# ant2-usb-c-lipo-charger.net
KiCad netlist of a schematic drawn in Altium Designer
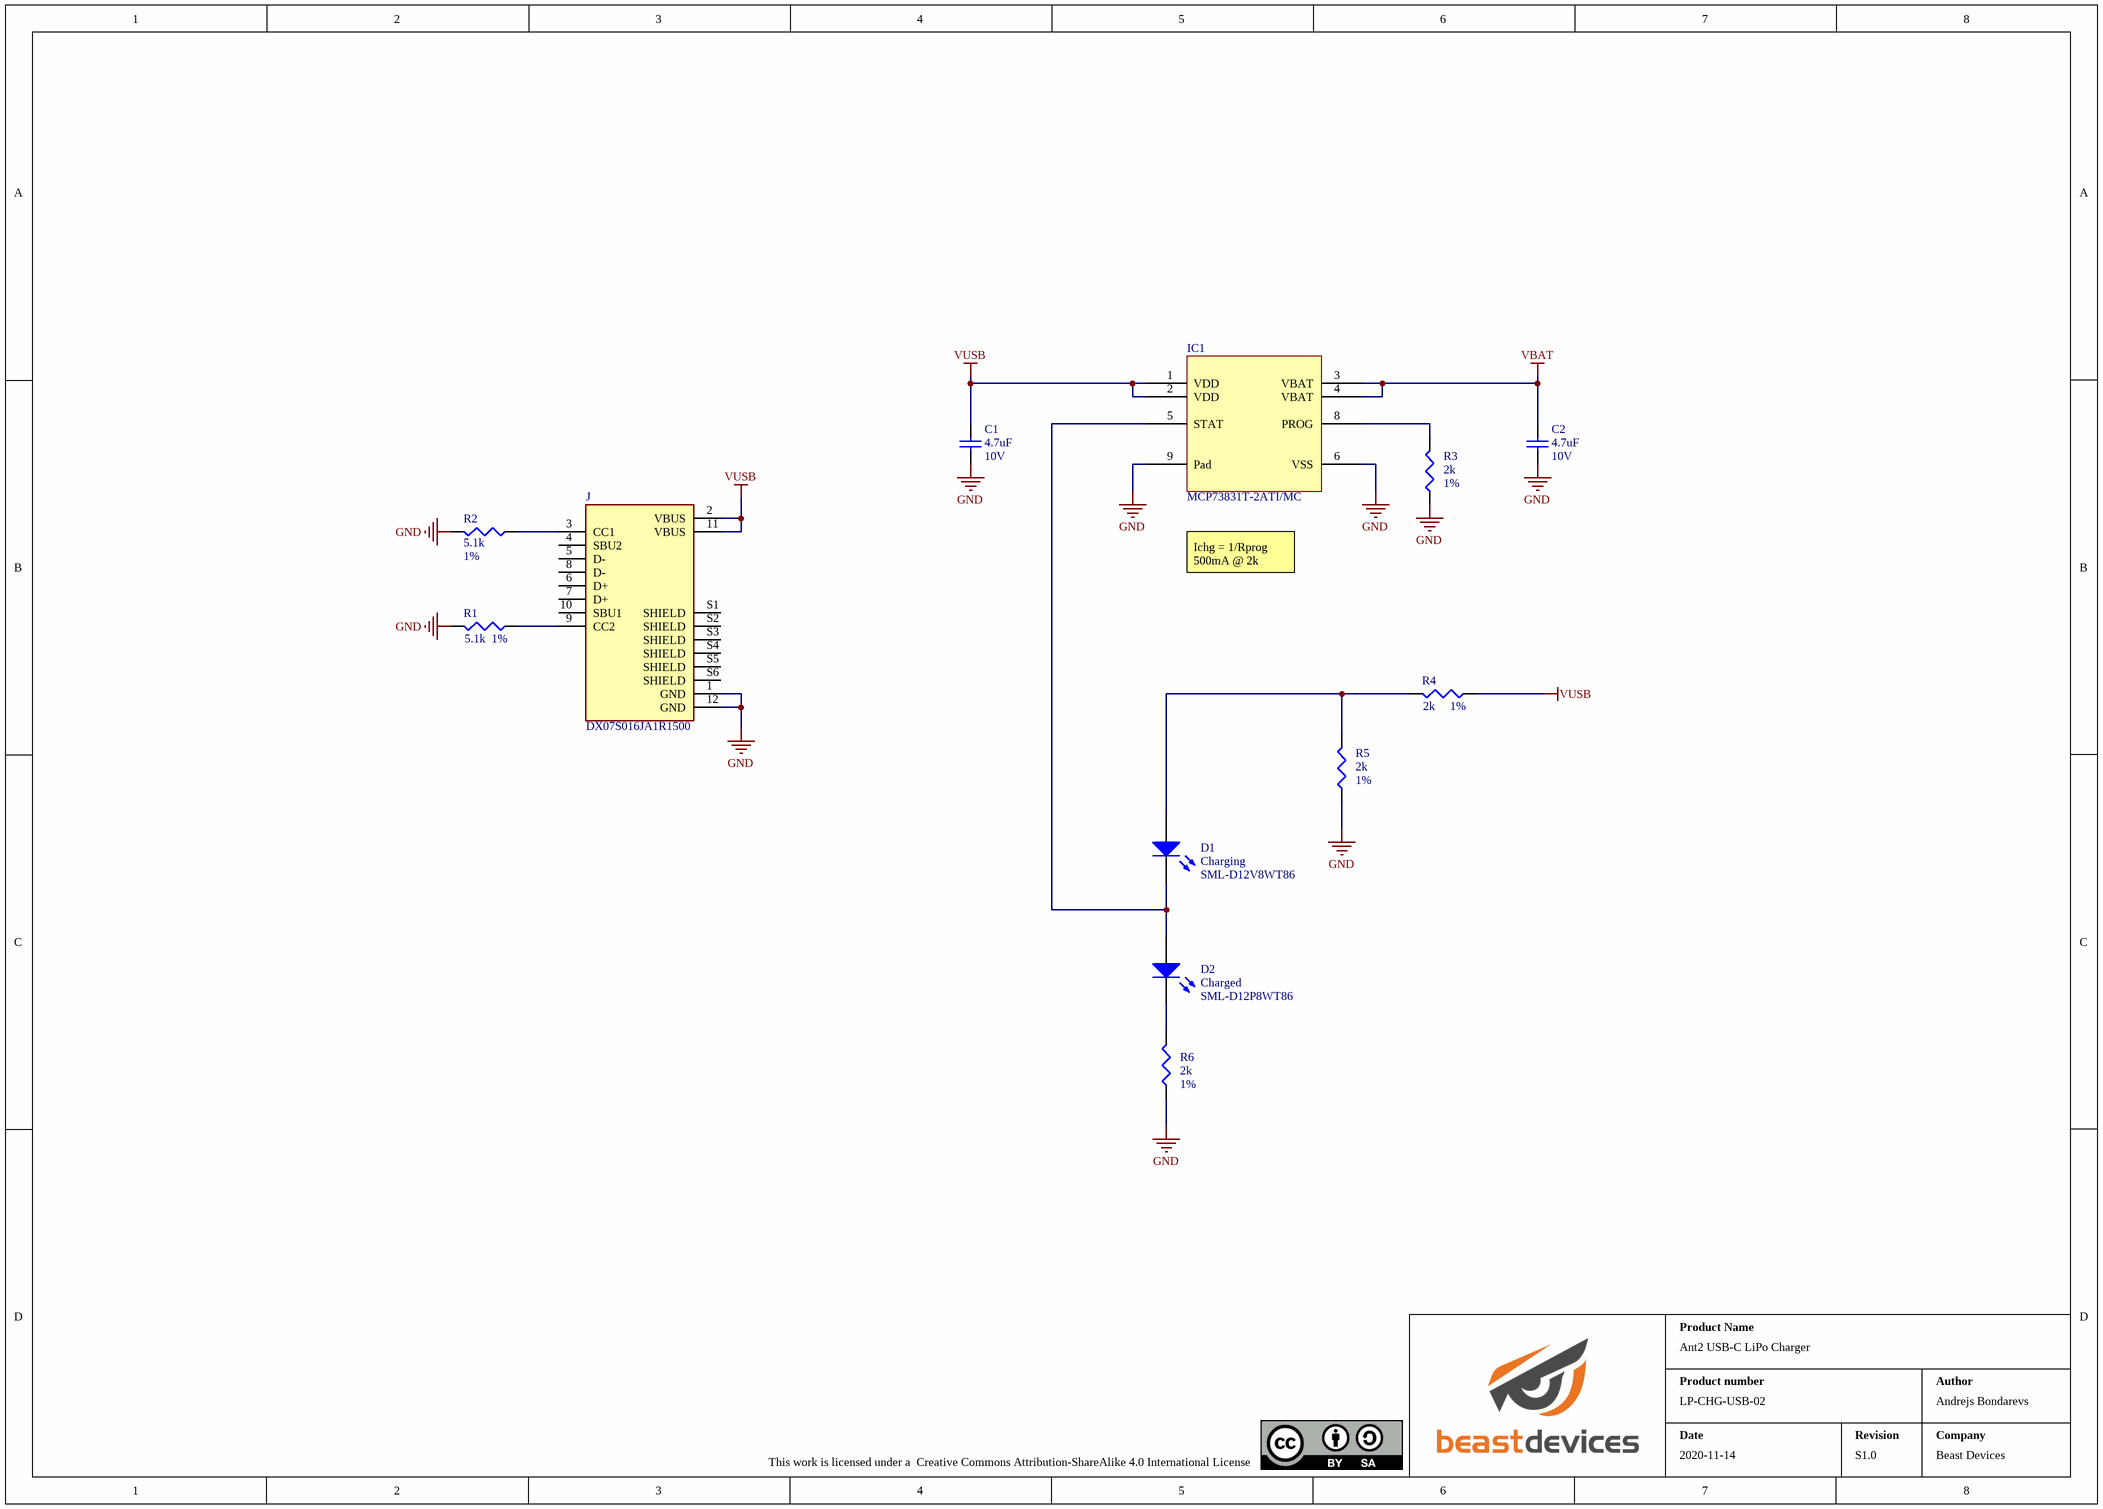
[diagram p0: ant2-usb-c-lipo-charger.SchDoc]

(export (version "E")
  (design (tool "Eeschema 10.0.6"))
  (components
    (comp (ref "C1")
      (value "4.7uF")
      (footprint "1608[0603]")
      (description "Capacitor (Semiconductor SIM Model)")
      (fields
        (field (name "VOLTAGE") "10V")
        (field (name "MANUFACTURER") "TDK")
        (field (name "PART NUMBER") "C1608X5R1A475K080AE")
      )
      (libsource (lib "Miscellaneous Devices") (part "Cap Semi"))
    )
    (comp (ref "C2")
      (value "4.7uF")
      (footprint "1608[0603]")
      (description "Capacitor (Semiconductor SIM Model)")
      (fields
        (field (name "VOLTAGE") "10V")
        (field (name "MANUFACTURER") "TDK")
        (field (name "PART NUMBER") "C1608X5R1A475K080AE")
      )
      (libsource (lib "Miscellaneous Devices") (part "Cap Semi"))
    )
    (comp (ref "D1")
      (value "Charging")
      (footprint "LED0603")
      (description "0603 SMD LED RED")
      (fields (field (name "MANUFACTURER") "ROHM Semiconductor") (field (name "PART NUMBER") "SML-D12V8WT86"))
      (libsource (lib "Miscellaneous Devices") (part "LED2"))
    )
    (comp (ref "D2")
      (value "Charged")
      (footprint "LED0603")
      (description "0603 SMD LED Green")
      (fields (field (name "MANUFACTURER") "ROHM Semiconductor") (field (name "PART NUMBER") "SML-D12P8WT86"))
      (libsource (lib "Miscellaneous Devices") (part "LED2"))
    )
    (comp (ref "IC1")
      (value "MCP73831")
      (footprint "DFN2x3_8Lead")
      (fields (field (name "MANUFACTURER") "Microchip") (field (name "PART NUMBER") "MCP73831T-2ATI/MC"))
      (libsource (lib "my_sch_lib") (part "MCP73831"))
    )
    (comp (ref "J")
      (value "DX07S016JA1R1500")
      (footprint "JAE_DX07S016JA1R1500")
      (fields (field (name "MANUFACTURER") "JAE Electronics"))
      (libsource (lib "DX07S016JA1R1500") (part "DX07S016JA1R1500"))
    )
    (comp (ref "R1")
      (value "5.1k")
      (footprint "J1-0603")
      (description "Resistor")
      (fields
        (field (name "MANUFACTURER") "Yageo")
        (field (name "PART NUMBER") "RC0603FR-075K1L")
        (field (name "TOLERANCE") "1%")
      )
      (libsource (lib "Miscellaneous Devices") (part "Res3"))
    )
    (comp (ref "R2")
      (value "5.1k")
      (footprint "J1-0603")
      (description "Resistor")
      (fields
        (field (name "PART NUMBER") "RC0603FR-075K1L")
        (field (name "MANUFACTURER") "Yageo")
        (field (name "TOLERANCE") "1%")
      )
      (libsource (lib "Miscellaneous Devices") (part "Res3"))
    )
    (comp (ref "R3")
      (value "2k")
      (footprint "J1-0603")
      (description "Resistor")
      (fields
        (field (name "MANUFACTURER") "Yageo")
        (field (name "PART NUMBER") "RC0603FR-072KL")
        (field (name "TOLERANCE") "1%")
      )
      (libsource (lib "Miscellaneous Devices") (part "Res3"))
    )
    (comp (ref "R4")
      (value "2k")
      (footprint "J1-0603")
      (description "Resistor")
      (fields
        (field (name "MANUFACTURER") "Vishay")
        (field (name "PART NUMBER") "RC0603FR-072KL")
        (field (name "TOLERANCE") "1%")
      )
      (libsource (lib "Miscellaneous Devices") (part "Res3"))
    )
    (comp (ref "R5")
      (value "2k")
      (footprint "J1-0603")
      (description "Resistor")
      (fields
        (field (name "MANUFACTURER") "Yageo")
        (field (name "PART NUMBER") "RC0603FR-072KL")
        (field (name "TOLERANCE") "1%")
      )
      (libsource (lib "Miscellaneous Devices") (part "Res3"))
    )
    (comp (ref "R6")
      (value "2k")
      (footprint "J1-0603")
      (description "Resistor")
      (fields
        (field (name "MANUFACTURER") "Yageo")
        (field (name "PART NUMBER") "RC0603FR-072KL")
        (field (name "TOLERANCE") "1%")
      )
      (libsource (lib "Miscellaneous Devices") (part "Res3"))
    )
  )
  (nets
    (net (code "1") (name "GND") (class "Default")
      (node (ref "C1") (pin "1") (pinfunction "1_1") (pintype "passive"))
      (node (ref "C2") (pin "1") (pinfunction "1_1") (pintype "passive"))
      (node (ref "IC1") (pin "6") (pinfunction "VSS_6") (pintype "passive"))
      (node (ref "IC1") (pin "9") (pinfunction "Pad_9") (pintype "passive"))
      (node (ref "J") (pin "1") (pinfunction "GND_1") (pintype "power_in"))
      (node (ref "J") (pin "12") (pinfunction "GND_12") (pintype "power_in"))
      (node (ref "R1") (pin "2") (pinfunction "2_2") (pintype "passive"))
      (node (ref "R2") (pin "1") (pinfunction "1_1") (pintype "passive"))
      (node (ref "R3") (pin "1") (pinfunction "1_1") (pintype "passive"))
      (node (ref "R5") (pin "1") (pinfunction "1_1") (pintype "passive"))
      (node (ref "R6") (pin "1") (pinfunction "1_1") (pintype "passive"))
    )
    (net (code "2") (name "Net-(D1-A)") (class "Default")
      (node (ref "D1") (pin "1") (pinfunction "A_1") (pintype "passive"))
      (node (ref "R4") (pin "2") (pinfunction "2_2") (pintype "passive"))
      (node (ref "R5") (pin "2") (pinfunction "2_2") (pintype "passive"))
    )
    (net (code "3") (name "Net-(D1-K)") (class "Default")
      (node (ref "D1") (pin "2") (pinfunction "K_2") (pintype "passive"))
      (node (ref "D2") (pin "1") (pinfunction "A_1") (pintype "passive"))
      (node (ref "IC1") (pin "5") (pinfunction "STAT_5") (pintype "passive"))
    )
    (net (code "4") (name "Net-(D2-K)") (class "Default")
      (node (ref "D2") (pin "2") (pinfunction "K_2") (pintype "passive"))
      (node (ref "R6") (pin "2") (pinfunction "2_2") (pintype "passive"))
    )
    (net (code "5") (name "Net-(IC1-PROG)") (class "Default")
      (node (ref "IC1") (pin "8") (pinfunction "PROG_8") (pintype "passive"))
      (node (ref "R3") (pin "2") (pinfunction "2_2") (pintype "passive"))
    )
    (net (code "6") (name "Net-(J-CC1)") (class "Default")
      (node (ref "J") (pin "3") (pinfunction "CC1_3") (pintype "passive"))
      (node (ref "R2") (pin "2") (pinfunction "2_2") (pintype "passive"))
    )
    (net (code "7") (name "Net-(J-CC2)") (class "Default")
      (node (ref "J") (pin "9") (pinfunction "CC2_9") (pintype "passive"))
      (node (ref "R1") (pin "1") (pinfunction "1_1") (pintype "passive"))
    )
    (net (code "8") (name "VBAT") (class "Default")
      (node (ref "C2") (pin "2") (pinfunction "2_2") (pintype "passive"))
      (node (ref "IC1") (pin "3") (pinfunction "VBAT_3") (pintype "passive"))
      (node (ref "IC1") (pin "4") (pinfunction "VBAT_4") (pintype "passive"))
    )
    (net (code "9") (name "VUSB") (class "Default")
      (node (ref "C1") (pin "2") (pinfunction "2_2") (pintype "passive"))
      (node (ref "IC1") (pin "1") (pinfunction "VDD_1") (pintype "passive"))
      (node (ref "IC1") (pin "2") (pinfunction "VDD_2") (pintype "passive"))
      (node (ref "J") (pin "11") (pinfunction "VBUS_11") (pintype "power_in"))
      (node (ref "J") (pin "2") (pinfunction "VBUS_2") (pintype "power_in"))
      (node (ref "R4") (pin "1") (pinfunction "1_1") (pintype "passive"))
    )
    (net (code "10") (name "unconnected-(J-D+-Pad6)") (class "Default")
      (node (ref "J") (pin "6") (pinfunction "D+_6") (pintype "passive"))
    )
    (net (code "11") (name "unconnected-(J-D+-Pad7)") (class "Default")
      (node (ref "J") (pin "7") (pinfunction "D+_7") (pintype "passive"))
    )
    (net (code "12") (name "unconnected-(J-D--Pad5)") (class "Default")
      (node (ref "J") (pin "5") (pinfunction "D-_5") (pintype "passive"))
    )
    (net (code "13") (name "unconnected-(J-D--Pad8)") (class "Default")
      (node (ref "J") (pin "8") (pinfunction "D-_8") (pintype "passive"))
    )
    (net (code "14") (name "unconnected-(J-SBU1-Pad10)") (class "Default")
      (node (ref "J") (pin "10") (pinfunction "SBU1_10") (pintype "passive"))
    )
    (net (code "15") (name "unconnected-(J-SBU2-Pad4)") (class "Default")
      (node (ref "J") (pin "4") (pinfunction "SBU2_4") (pintype "passive"))
    )
    (net (code "16") (name "unconnected-(J-SHIELD-PadS1)") (class "Default")
      (node (ref "J") (pin "S1") (pinfunction "SHIELD_S1") (pintype "passive"))
    )
    (net (code "17") (name "unconnected-(J-SHIELD-PadS2)") (class "Default")
      (node (ref "J") (pin "S2") (pinfunction "SHIELD_S2") (pintype "passive"))
    )
    (net (code "18") (name "unconnected-(J-SHIELD-PadS3)") (class "Default")
      (node (ref "J") (pin "S3") (pinfunction "SHIELD_S3") (pintype "passive"))
    )
    (net (code "19") (name "unconnected-(J-SHIELD-PadS4)") (class "Default")
      (node (ref "J") (pin "S4") (pinfunction "SHIELD_S4") (pintype "passive"))
    )
    (net (code "20") (name "unconnected-(J-SHIELD-PadS5)") (class "Default")
      (node (ref "J") (pin "S5") (pinfunction "SHIELD_S5") (pintype "passive"))
    )
    (net (code "21") (name "unconnected-(J-SHIELD-PadS6)") (class "Default")
      (node (ref "J") (pin "S6") (pinfunction "SHIELD_S6") (pintype "passive"))
    )
  )
)
